# Test.net
KiCad netlist of a schematic drawn in Altium Designer
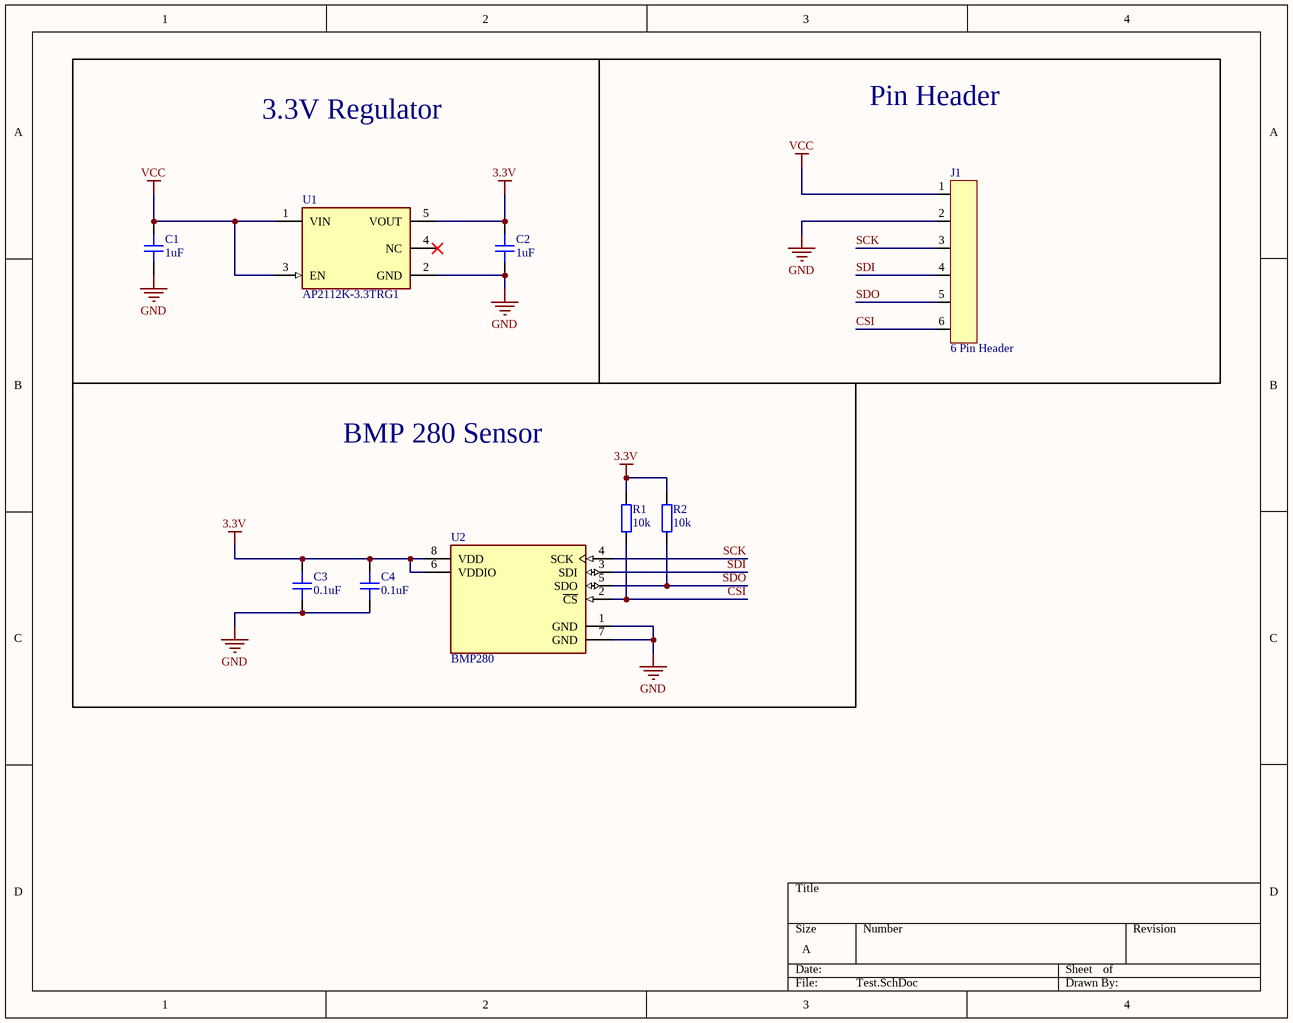
[diagram p0: Test.SchDoc]

(export (version "E")
  (design (tool "Eeschema 10.0.6"))
  (components
    (comp (ref "C1")
      (value "1uF")
      (footprint "CAP_0805")
      (description "Capacitor SMD 0805")
      (libsource (lib "Schematic-Lib-PhilsLab") (part "CAP_0805"))
    )
    (comp (ref "C2")
      (value "1uF")
      (footprint "CAP_0805")
      (description "Capacitor SMD 0805")
      (libsource (lib "Schematic-Lib-PhilsLab") (part "CAP_0805"))
    )
    (comp (ref "C3")
      (value "0.1uF")
      (footprint "CAP_0603")
      (description "Capacitor SMD 0603")
      (libsource (lib "Schematic-Lib-PhilsLab") (part "CAP_0603"))
    )
    (comp (ref "C4")
      (value "0.1uF")
      (footprint "CAP_0603")
      (description "Capacitor SMD 0603")
      (libsource (lib "Schematic-Lib-PhilsLab") (part "CAP_0603"))
    )
    (comp (ref "J1")
      (value "6 Pin Header")
      (footprint "G800W302018EU")
      (description "Pin Header 6 Position 2.54mm Pitch")
      (fields
        (field (name "MANUFACTURER") "Amphenol")
        (field (name "MANUFACTURER PART NUMBER") "G800W302018EU")
      )
      (libsource (lib "Schematic-Lib-PhilsLab") (part "G800W302018EU"))
    )
    (comp (ref "R1")
      (value "10k")
      (footprint "RES_0603")
      (description "Resistor SMD 0603")
      (libsource (lib "Schematic-Lib-PhilsLab") (part "RES_0603"))
    )
    (comp (ref "R2")
      (value "10k")
      (footprint "RES_0603")
      (description "Resistor SMD 0603")
      (libsource (lib "Schematic-Lib-PhilsLab") (part "RES_0603"))
    )
    (comp (ref "U1")
      (value "AP2112K-3.3TRG1")
      (footprint "FP-SOT25-IPC_A")
      (description "IC REG LINEAR 3.3V 600MA SOT25")
      (libsource (lib "Altium Content Vault") (part "c8ab751aee5229183125ab046a11caa"))
    )
    (comp (ref "U2")
      (value "BMP280")
      (footprint "FP-BMP280-MFG")
      (description "SENSOR PRESSURE ABS")
      (libsource (lib "Altium Content Vault") (part "69b1aacbb03d82763a43fac02afba64"))
    )
  )
  (nets
    (net (code "1") (name "/CSI") (class "Default")
      (node (ref "J1") (pin "6") (pinfunction "6_6") (pintype "passive"))
      (node (ref "R1") (pin "1") (pinfunction "1_1") (pintype "passive"))
      (node (ref "U2") (pin "2") (pinfunction "~{CS}_2") (pintype "input"))
    )
    (net (code "2") (name "/SCK") (class "Default")
      (node (ref "J1") (pin "3") (pinfunction "3_3") (pintype "passive"))
      (node (ref "U2") (pin "4") (pinfunction "SCK_4") (pintype "input"))
    )
    (net (code "3") (name "/SDI") (class "Default")
      (node (ref "J1") (pin "4") (pinfunction "4_4") (pintype "passive"))
      (node (ref "U2") (pin "3") (pinfunction "SDI_3") (pintype "bidirectional"))
    )
    (net (code "4") (name "/SDO") (class "Default")
      (node (ref "J1") (pin "5") (pinfunction "5_5") (pintype "passive"))
      (node (ref "R2") (pin "1") (pinfunction "1_1") (pintype "passive"))
      (node (ref "U2") (pin "5") (pinfunction "SDO_5") (pintype "bidirectional"))
    )
    (net (code "5") (name "3.3V") (class "Default")
      (node (ref "C2") (pin "2") (pinfunction "2_2") (pintype "passive"))
      (node (ref "C3") (pin "2") (pinfunction "2_2") (pintype "passive"))
      (node (ref "C4") (pin "2") (pinfunction "2_2") (pintype "passive"))
      (node (ref "R1") (pin "2") (pinfunction "2_2") (pintype "passive"))
      (node (ref "R2") (pin "2") (pinfunction "2_2") (pintype "passive"))
      (node (ref "U1") (pin "5") (pinfunction "VOUT_5") (pintype "power_in"))
      (node (ref "U2") (pin "6") (pinfunction "VDDIO_6") (pintype "power_in"))
      (node (ref "U2") (pin "8") (pinfunction "VDD_8") (pintype "power_in"))
    )
    (net (code "6") (name "GND") (class "Default")
      (node (ref "C1") (pin "1") (pinfunction "1_1") (pintype "passive"))
      (node (ref "C2") (pin "1") (pinfunction "1_1") (pintype "passive"))
      (node (ref "C3") (pin "1") (pinfunction "1_1") (pintype "passive"))
      (node (ref "C4") (pin "1") (pinfunction "1_1") (pintype "passive"))
      (node (ref "J1") (pin "2") (pinfunction "2_2") (pintype "passive"))
      (node (ref "U1") (pin "2") (pinfunction "GND_2") (pintype "power_in"))
      (node (ref "U2") (pin "1") (pinfunction "GND_1") (pintype "power_in"))
      (node (ref "U2") (pin "7") (pinfunction "GND_7") (pintype "power_in"))
    )
    (net (code "7") (name "VCC") (class "Default")
      (node (ref "C1") (pin "2") (pinfunction "2_2") (pintype "passive"))
      (node (ref "J1") (pin "1") (pinfunction "1_1") (pintype "passive"))
      (node (ref "U1") (pin "1") (pinfunction "VIN_1") (pintype "power_in"))
      (node (ref "U1") (pin "3") (pinfunction "EN_3") (pintype "input"))
    )
    (net (code "8") (name "unconnected-(U1-NC-Pad4)") (class "Default")
      (node (ref "U1") (pin "4") (pinfunction "NC_4") (pintype "passive+no_connect"))
    )
  )
)
